# HshMain_v1_2.net
KiCad netlist of a schematic drawn in EAGLE
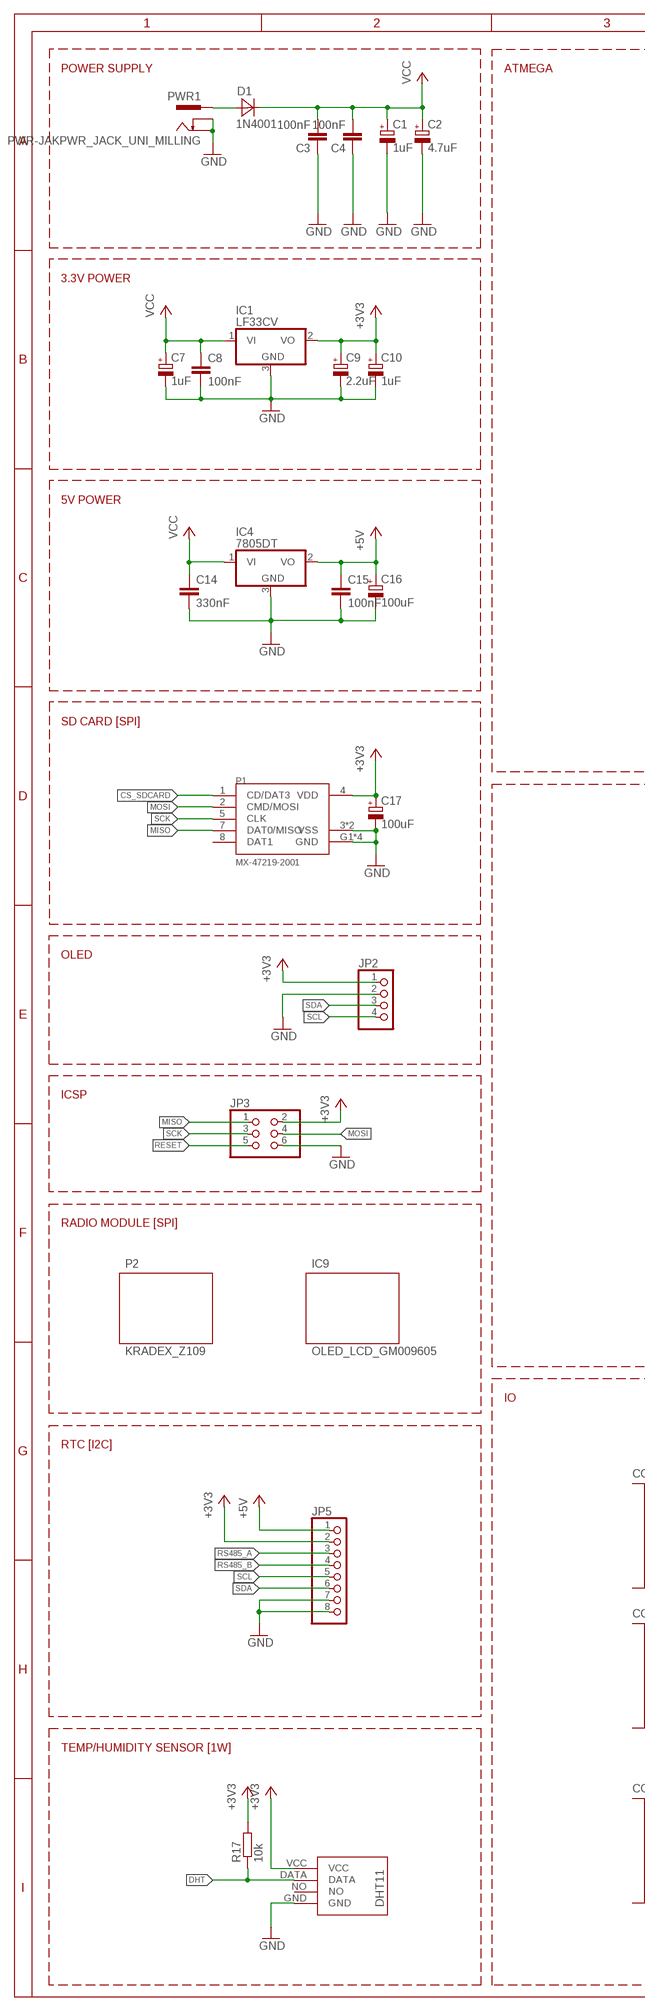
[diagram p0: schematic, sheet 1, part 1 of 2]
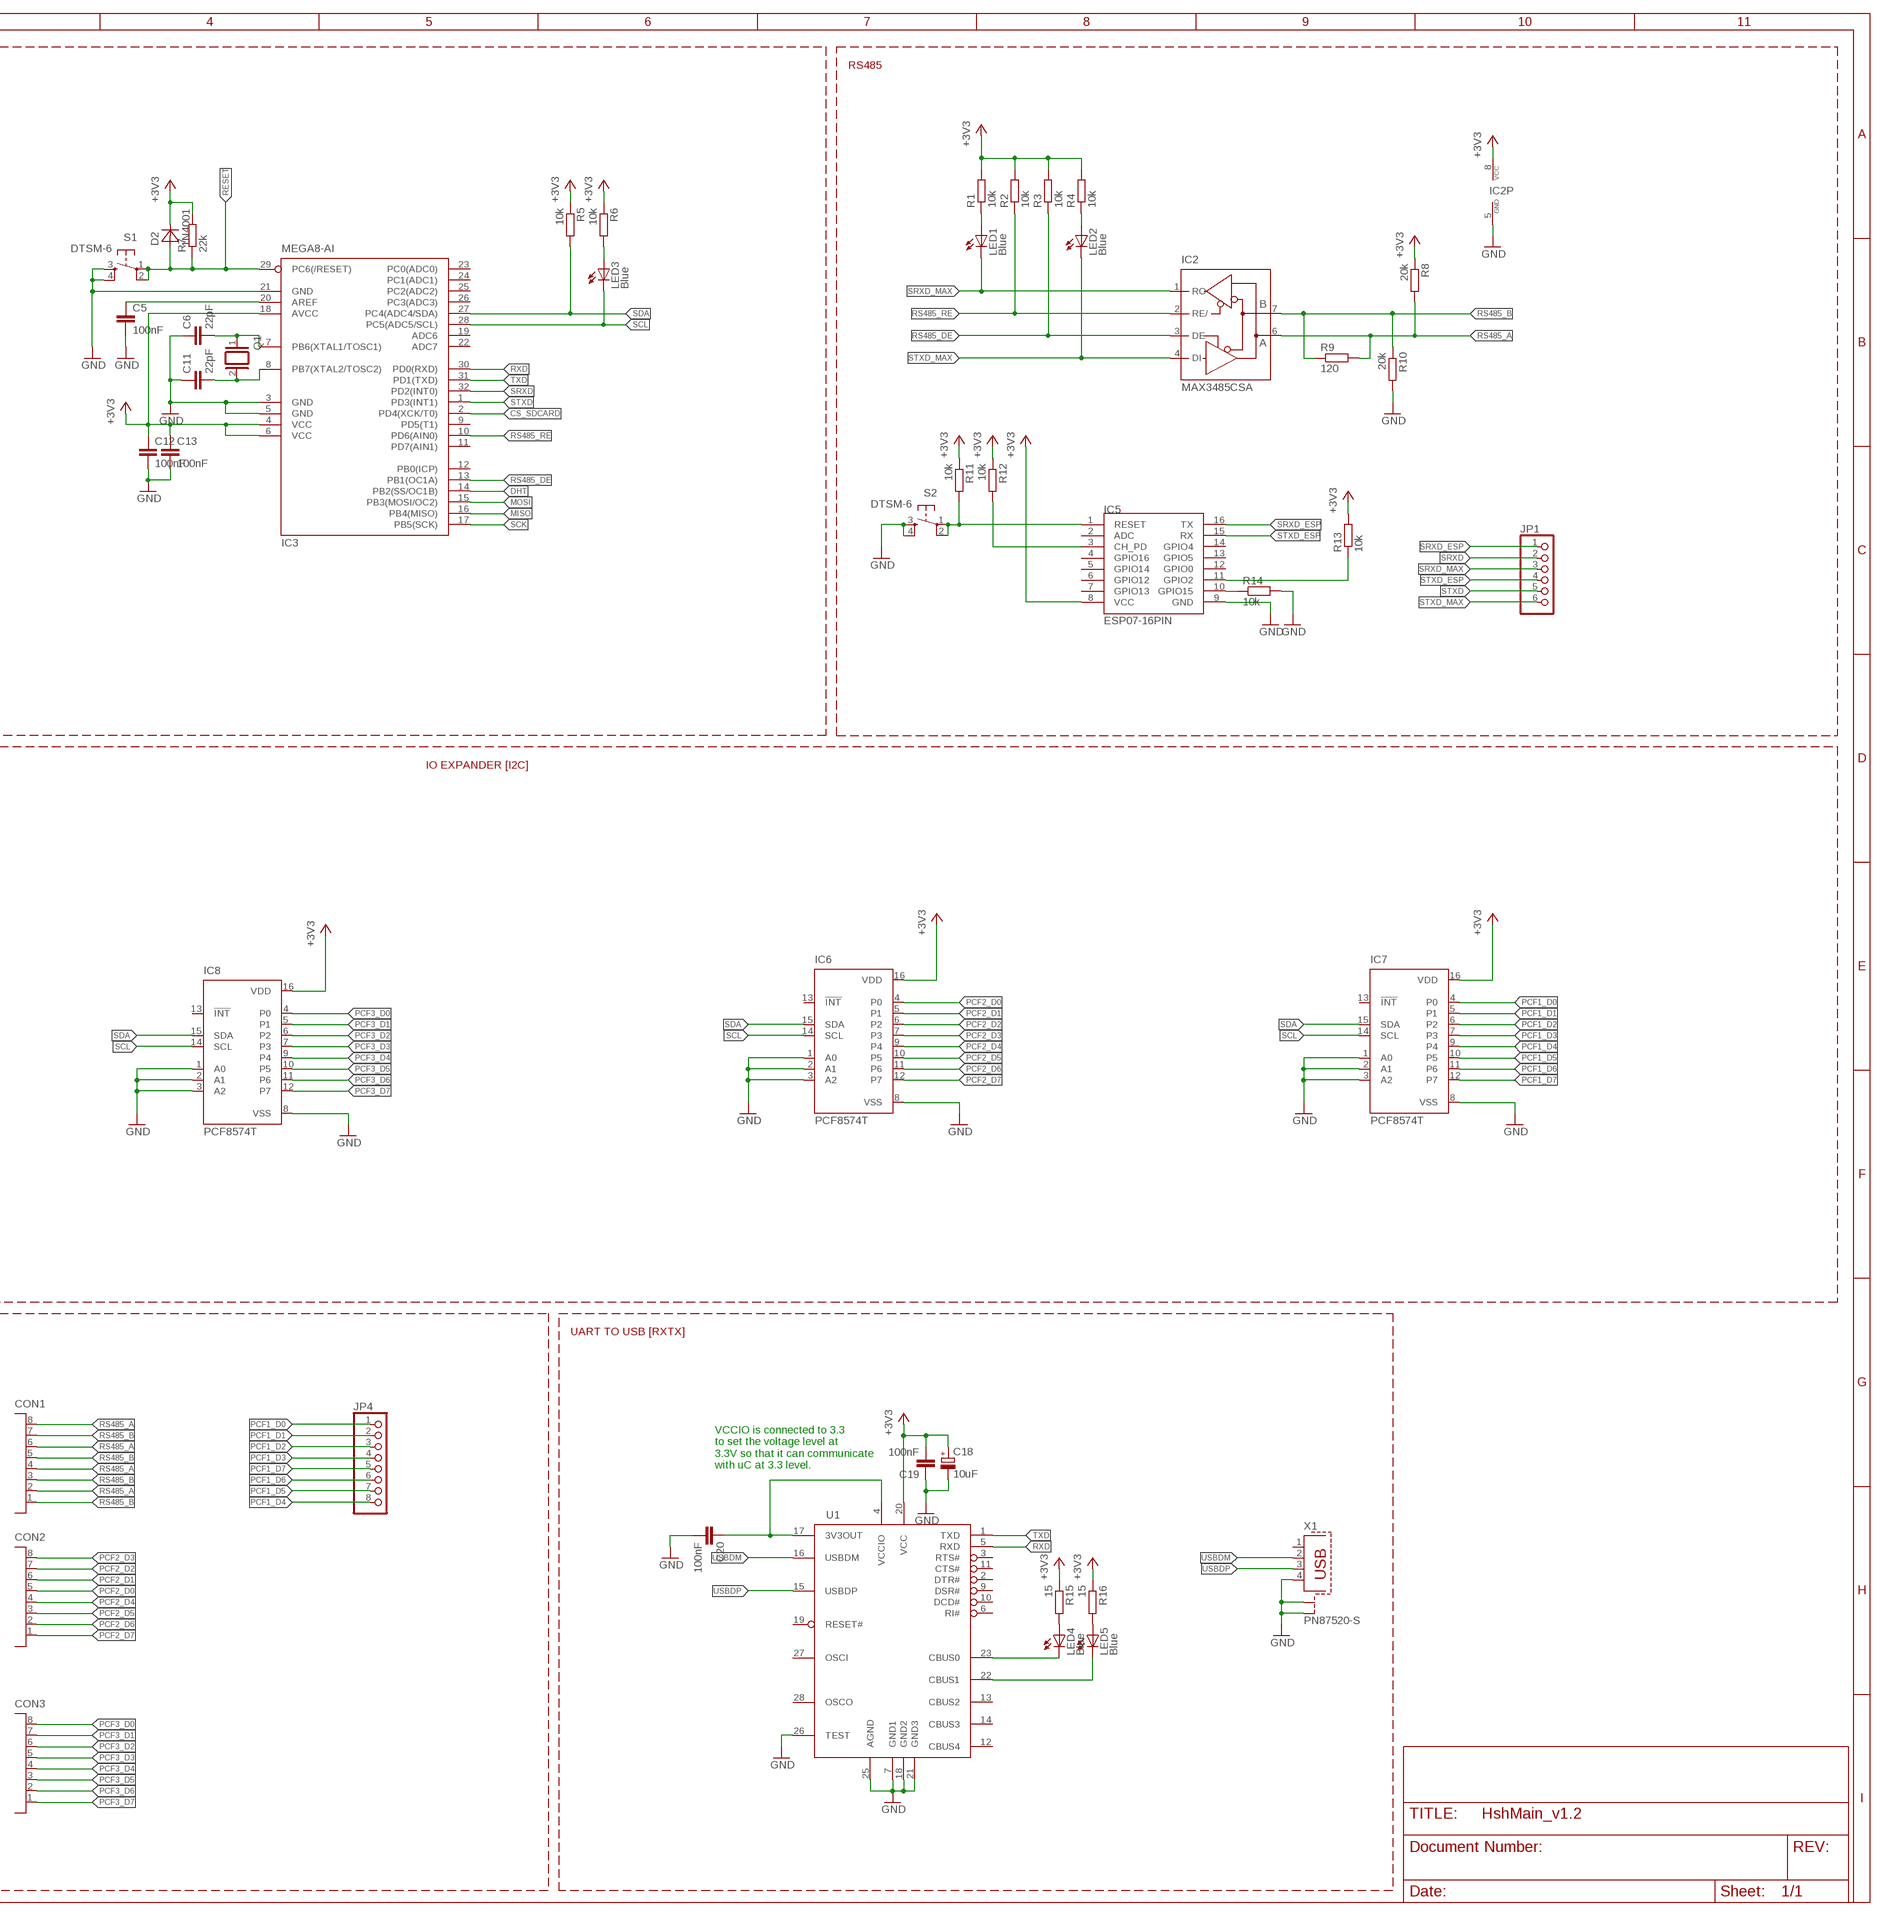
[diagram p1: schematic, sheet 1, part 2 of 2]

(export (version "E")
  (design (tool "Eeschema 10.0.6"))
  (components
    (comp (ref "C1")
      (value "1uF")
      (footprint "eagle-import:PANASONIC_B")
      (libsource (lib "eagle-import") (part "CPOL-EUB"))
    )
    (comp (ref "C2")
      (value "4.7uF")
      (footprint "eagle-import:PANASONIC_B")
      (libsource (lib "eagle-import") (part "CPOL-EUB"))
    )
    (comp (ref "C3")
      (value "100nF")
      (footprint "eagle-import:C0805")
      (libsource (lib "eagle-import") (part "C-EUC0805"))
    )
    (comp (ref "C4")
      (value "100nF")
      (footprint "eagle-import:C0805")
      (libsource (lib "eagle-import") (part "C-EUC0805"))
    )
    (comp (ref "C5")
      (value "100nF")
      (footprint "eagle-import:C0805")
      (libsource (lib "eagle-import") (part "C-EUC0805"))
    )
    (comp (ref "C6")
      (value "22pF")
      (footprint "eagle-import:C0805")
      (libsource (lib "eagle-import") (part "C-EUC0805"))
    )
    (comp (ref "C7")
      (value "1uF")
      (footprint "eagle-import:PANASONIC_B")
      (libsource (lib "eagle-import") (part "CPOL-EUB"))
    )
    (comp (ref "C8")
      (value "100nF")
      (footprint "eagle-import:C0805")
      (libsource (lib "eagle-import") (part "C-EUC0805"))
    )
    (comp (ref "C9")
      (value "2.2uF")
      (footprint "eagle-import:PANASONIC_B")
      (libsource (lib "eagle-import") (part "CPOL-EUB"))
    )
    (comp (ref "C10")
      (value "1uF")
      (footprint "eagle-import:PANASONIC_B")
      (libsource (lib "eagle-import") (part "CPOL-EUB"))
    )
    (comp (ref "C11")
      (value "22pF")
      (footprint "eagle-import:C0805")
      (libsource (lib "eagle-import") (part "C-EUC0805"))
    )
    (comp (ref "C12")
      (value "100nF")
      (footprint "eagle-import:C0805")
      (libsource (lib "eagle-import") (part "C-EUC0805"))
    )
    (comp (ref "C13")
      (value "100nF")
      (footprint "eagle-import:C0805")
      (libsource (lib "eagle-import") (part "C-EUC0805"))
    )
    (comp (ref "C14")
      (value "330nF")
      (footprint "eagle-import:C0805")
      (libsource (lib "eagle-import") (part "C-EUC0805"))
    )
    (comp (ref "C15")
      (value "100nF")
      (footprint "eagle-import:C0805")
      (libsource (lib "eagle-import") (part "C-EUC0805"))
    )
    (comp (ref "C16")
      (value "100uF")
      (footprint "eagle-import:PANASONIC_D")
      (libsource (lib "eagle-import") (part "CPOL-EUD"))
    )
    (comp (ref "C17")
      (value "100uF")
      (footprint "eagle-import:PANASONIC_D")
      (libsource (lib "eagle-import") (part "CPOL-EUD"))
    )
    (comp (ref "C18")
      (value "10uF")
      (footprint "eagle-import:PANASONIC_B")
      (libsource (lib "eagle-import") (part "CPOL-EUB"))
    )
    (comp (ref "C19")
      (value "100nF")
      (footprint "eagle-import:C0805")
      (libsource (lib "eagle-import") (part "C-EUC0805"))
    )
    (comp (ref "C20")
      (value "100nF")
      (footprint "eagle-import:C0805")
      (libsource (lib "eagle-import") (part "C-EUC0805"))
    )
    (comp (ref "CON1")
      (value "15EDGRC-3.81-8P")
      (footprint "eagle-import:15EDGRC-3.81-8P")
      (libsource (lib "eagle-import") (part "15EDGRC-3.81-8P"))
    )
    (comp (ref "CON2")
      (value "15EDGRC-3.81-8P")
      (footprint "eagle-import:15EDGRC-3.81-8P")
      (libsource (lib "eagle-import") (part "15EDGRC-3.81-8P"))
    )
    (comp (ref "CON3")
      (value "15EDGRC-3.81-8P")
      (footprint "eagle-import:15EDGRC-3.81-8P")
      (libsource (lib "eagle-import") (part "15EDGRC-3.81-8P"))
    )
    (comp (ref "D1")
      (value "1N4001")
      (footprint "eagle-import:SMA")
      (libsource (lib "eagle-import") (part "MBRA340T3"))
    )
    (comp (ref "D2")
      (value "1N4001")
      (footprint "eagle-import:SMA")
      (libsource (lib "eagle-import") (part "MBRA340T3"))
    )
    (comp (ref "IC1")
      (value "LF33CV")
      (footprint "eagle-import:TO252")
      (libsource (lib "eagle-import") (part "78DT"))
    )
    (comp (ref "IC2")
      (value "MAX3485CSA")
      (footprint "eagle-import:SO08")
      (fields (field (name "MF") "MAXIM") (field (name "MPN") "MAX481CSA"))
      (libsource (lib "eagle-import") (part "MAX481CSA"))
    )
    (comp (ref "IC3")
      (value "MEGA8-AI")
      (footprint "eagle-import:TQFP32-08")
      (fields (field (name "MPN") "ATMEGA8-16AU"))
      (libsource (lib "eagle-import") (part "MEGA8-AI"))
    )
    (comp (ref "IC4")
      (value "7805DT")
      (footprint "eagle-import:TO252")
      (libsource (lib "eagle-import") (part "linear_78DT05"))
    )
    (comp (ref "IC5")
      (value "ESP07-16PIN")
      (footprint "eagle-import:ESP07-16PIN")
      (libsource (lib "eagle-import") (part "ESP07-16PIN"))
    )
    (comp (ref "IC6")
      (value "PCF8574T")
      (footprint "eagle-import:SO16W")
      (fields (field (name "MPN") "PCF8574T/3,512"))
      (libsource (lib "eagle-import") (part "PCF8574T"))
    )
    (comp (ref "IC7")
      (value "PCF8574T")
      (footprint "eagle-import:SO16W")
      (fields (field (name "MPN") "PCF8574T/3,512"))
      (libsource (lib "eagle-import") (part "PCF8574T"))
    )
    (comp (ref "IC8")
      (value "PCF8574T")
      (footprint "eagle-import:SO16W")
      (fields (field (name "MPN") "PCF8574T/3,512"))
      (libsource (lib "eagle-import") (part "PCF8574T"))
    )
    (comp (ref "IC9")
      (value "OLED_LCD_GM009605")
      (footprint "eagle-import:OLED_LCD_GM009605")
      (libsource (lib "eagle-import") (part "OLED_LCD_GM009605"))
    )
    (comp (ref "IC10")
      (value "DHT11-PION.")
      (footprint "eagle-import:DHT11-PION.")
      (libsource (lib "eagle-import") (part "DHT11-PION."))
    )
    (comp (ref "JP1")
      (value "PINHD-1X6")
      (footprint "eagle-import:1X06")
      (libsource (lib "eagle-import") (part "PINHD-1X6"))
    )
    (comp (ref "JP2")
      (value "PINHD-1X4")
      (footprint "eagle-import:1X04")
      (libsource (lib "eagle-import") (part "PINHD-1X4"))
    )
    (comp (ref "JP3")
      (value "PINHD-2X3")
      (footprint "eagle-import:2X03")
      (libsource (lib "eagle-import") (part "PINHD-2X3"))
    )
    (comp (ref "JP4")
      (value "PINHD-1X8")
      (footprint "eagle-import:1X08")
      (libsource (lib "eagle-import") (part "PINHD-1X8"))
    )
    (comp (ref "JP5")
      (value "PINHD-1X8/90")
      (footprint "eagle-import:1X08_90")
      (libsource (lib "eagle-import") (part "PINHD-1X8/90"))
    )
    (comp (ref "LED1")
      (value "Blue")
      (footprint "eagle-import:SML0805")
      (libsource (lib "eagle-import") (part "LEDSML0805"))
    )
    (comp (ref "LED2")
      (value "Blue")
      (footprint "eagle-import:SML0805")
      (libsource (lib "eagle-import") (part "LEDSML0805"))
    )
    (comp (ref "LED3")
      (value "Blue")
      (footprint "eagle-import:SML0805")
      (libsource (lib "eagle-import") (part "LEDSML0805"))
    )
    (comp (ref "LED4")
      (value "Blue")
      (footprint "eagle-import:SML0805")
      (libsource (lib "eagle-import") (part "LEDSML0805"))
    )
    (comp (ref "LED5")
      (value "Blue")
      (footprint "eagle-import:SML0805")
      (libsource (lib "eagle-import") (part "LEDSML0805"))
    )
    (comp (ref "P1")
      (value "MX-47219-2001")
      (footprint "eagle-import:MX-47219-2001")
      (libsource (lib "eagle-import") (part "MX-47219-2001"))
    )
    (comp (ref "P2")
      (value "KRADEX_Z109")
      (footprint "eagle-import:KRADEX_Z109")
      (libsource (lib "eagle-import") (part "KRADEX_Z109"))
    )
    (comp (ref "PWR1")
      (value "PWR-JAKPWR_JACK_UNI_MILLING")
      (footprint "eagle-import:PWR_JACK_UNI_MILLING")
      (libsource (lib "eagle-import") (part "PWR-JAKPWR_JACK_UNI_MILLING"))
    )
    (comp (ref "Q1")
      (value "XTAL/S")
      (footprint "eagle-import:QS")
      (libsource (lib "eagle-import") (part "XTAL/S"))
    )
    (comp (ref "R1")
      (value "10k")
      (footprint "eagle-import:R0805")
      (libsource (lib "eagle-import") (part "R-EU_R0805"))
    )
    (comp (ref "R2")
      (value "10k")
      (footprint "eagle-import:R0805")
      (libsource (lib "eagle-import") (part "R-EU_R0805"))
    )
    (comp (ref "R3")
      (value "10k")
      (footprint "eagle-import:R0805")
      (libsource (lib "eagle-import") (part "R-EU_R0805"))
    )
    (comp (ref "R4")
      (value "10k")
      (footprint "eagle-import:R0805")
      (libsource (lib "eagle-import") (part "R-EU_R0805"))
    )
    (comp (ref "R5")
      (value "10k")
      (footprint "eagle-import:R0805")
      (libsource (lib "eagle-import") (part "R-EU_R0805"))
    )
    (comp (ref "R6")
      (value "10k")
      (footprint "eagle-import:R0805")
      (libsource (lib "eagle-import") (part "R-EU_R0805"))
    )
    (comp (ref "R7")
      (value "22k")
      (footprint "eagle-import:R0805")
      (libsource (lib "eagle-import") (part "R-EU_R0805"))
    )
    (comp (ref "R8")
      (value "20k")
      (footprint "eagle-import:R0805")
      (libsource (lib "eagle-import") (part "R-EU_R0805"))
    )
    (comp (ref "R9")
      (value "120")
      (footprint "eagle-import:R0805")
      (libsource (lib "eagle-import") (part "R-EU_R0805"))
    )
    (comp (ref "R10")
      (value "20k")
      (footprint "eagle-import:R0805")
      (libsource (lib "eagle-import") (part "R-EU_R0805"))
    )
    (comp (ref "R11")
      (value "10k")
      (footprint "eagle-import:R0805")
      (libsource (lib "eagle-import") (part "R-EU_R0805"))
    )
    (comp (ref "R12")
      (value "10k")
      (footprint "eagle-import:R0805")
      (libsource (lib "eagle-import") (part "R-EU_R0805"))
    )
    (comp (ref "R13")
      (value "10k")
      (footprint "eagle-import:R0805")
      (libsource (lib "eagle-import") (part "R-EU_R0805"))
    )
    (comp (ref "R14")
      (value "10k")
      (footprint "eagle-import:R0805")
      (libsource (lib "eagle-import") (part "R-EU_R0805"))
    )
    (comp (ref "R15")
      (value "15")
      (footprint "eagle-import:R0805")
      (libsource (lib "eagle-import") (part "R-EU_R0805"))
    )
    (comp (ref "R16")
      (value "15")
      (footprint "eagle-import:R0805")
      (libsource (lib "eagle-import") (part "R-EU_R0805"))
    )
    (comp (ref "R17")
      (value "10k")
      (footprint "eagle-import:R0805")
      (libsource (lib "eagle-import") (part "R-EU_R0805"))
    )
    (comp (ref "S1")
      (value "DTSM-6")
      (footprint "eagle-import:DTSM-6")
      (libsource (lib "eagle-import") (part "DTSM-6"))
    )
    (comp (ref "S2")
      (value "DTSM-6")
      (footprint "eagle-import:DTSM-6")
      (libsource (lib "eagle-import") (part "DTSM-6"))
    )
    (comp (ref "U1")
      (value "FT232RL")
      (footprint "eagle-import:SSOP28DB")
      (libsource (lib "eagle-import") (part "FT232RL"))
    )
    (comp (ref "X1")
      (value "PN87520-S")
      (footprint "eagle-import:PN87520-S")
      (libsource (lib "eagle-import") (part "PN87520-S"))
    )
  )
  (nets
    (net (code "1") (name "+3V3") (class "Default")
      (node (ref "C10") (pin "+") (pinfunction "+_+") (pintype "passive"))
      (node (ref "C12") (pin "1") (pinfunction "1_1") (pintype "passive"))
      (node (ref "C13") (pin "1") (pinfunction "1_1") (pintype "passive"))
      (node (ref "C17") (pin "+") (pinfunction "+_+") (pintype "passive"))
      (node (ref "C18") (pin "+") (pinfunction "+_+") (pintype "passive"))
      (node (ref "C19") (pin "2") (pinfunction "2_2") (pintype "passive"))
      (node (ref "C9") (pin "+") (pinfunction "+_+") (pintype "passive"))
      (node (ref "D2") (pin "C") (pinfunction "C_C") (pintype "passive"))
      (node (ref "IC1") (pin "2") (pinfunction "VO_2") (pintype "passive"))
      (node (ref "IC10") (pin "VCC") (pinfunction "VCC_VCC") (pintype "bidirectional"))
      (node (ref "IC2") (pin "8") (pinfunction "VCC_8") (pintype "power_in"))
      (node (ref "IC3") (pin "18") (pinfunction "AVCC_18") (pintype "power_in"))
      (node (ref "IC3") (pin "4") (pinfunction "VCC_4") (pintype "power_in"))
      (node (ref "IC3") (pin "6") (pinfunction "VCC_6") (pintype "power_in"))
      (node (ref "IC5") (pin "8") (pinfunction "VCC_8") (pintype "bidirectional"))
      (node (ref "IC6") (pin "16") (pinfunction "VDD_16") (pintype "power_in"))
      (node (ref "IC7") (pin "16") (pinfunction "VDD_16") (pintype "power_in"))
      (node (ref "IC8") (pin "16") (pinfunction "VDD_16") (pintype "power_in"))
      (node (ref "JP2") (pin "1") (pinfunction "1_1") (pintype "passive"))
      (node (ref "JP3") (pin "2") (pinfunction "2_2") (pintype "passive"))
      (node (ref "JP5") (pin "2") (pinfunction "2_2") (pintype "passive"))
      (node (ref "P1") (pin "4") (pinfunction "VDD_4") (pintype "bidirectional"))
      (node (ref "R1") (pin "2") (pinfunction "2_2") (pintype "passive"))
      (node (ref "R11") (pin "1") (pinfunction "1_1") (pintype "passive"))
      (node (ref "R12") (pin "1") (pinfunction "1_1") (pintype "passive"))
      (node (ref "R13") (pin "2") (pinfunction "2_2") (pintype "passive"))
      (node (ref "R15") (pin "1") (pinfunction "1_1") (pintype "passive"))
      (node (ref "R16") (pin "1") (pinfunction "1_1") (pintype "passive"))
      (node (ref "R17") (pin "2") (pinfunction "2_2") (pintype "passive"))
      (node (ref "R2") (pin "2") (pinfunction "2_2") (pintype "passive"))
      (node (ref "R3") (pin "2") (pinfunction "2_2") (pintype "passive"))
      (node (ref "R4") (pin "2") (pinfunction "2_2") (pintype "passive"))
      (node (ref "R5") (pin "1") (pinfunction "1_1") (pintype "passive"))
      (node (ref "R6") (pin "1") (pinfunction "1_1") (pintype "passive"))
      (node (ref "R7") (pin "2") (pinfunction "2_2") (pintype "passive"))
      (node (ref "R8") (pin "1") (pinfunction "1_1") (pintype "passive"))
      (node (ref "U1") (pin "20") (pinfunction "VCC_20") (pintype "power_in"))
    )
    (net (code "2") (name "+5V") (class "Default")
      (node (ref "C15") (pin "1") (pinfunction "1_1") (pintype "passive"))
      (node (ref "C16") (pin "+") (pinfunction "+_+") (pintype "passive"))
      (node (ref "IC4") (pin "2") (pinfunction "VO_2") (pintype "passive"))
      (node (ref "JP5") (pin "1") (pinfunction "1_1") (pintype "passive"))
    )
    (net (code "3") (name "CS_SDCARD") (class "Default")
      (node (ref "IC3") (pin "2") (pinfunction "PD4(XCK/T0)_2") (pintype "bidirectional"))
      (node (ref "P1") (pin "1") (pinfunction "CD/DAT3_1") (pintype "bidirectional"))
    )
    (net (code "4") (name "DHT") (class "Default")
      (node (ref "IC10") (pin "DATA") (pinfunction "DATA_DATA") (pintype "bidirectional"))
      (node (ref "IC3") (pin "14") (pinfunction "PB2(SS/OC1B)_14") (pintype "bidirectional"))
      (node (ref "R17") (pin "1") (pinfunction "1_1") (pintype "passive"))
    )
    (net (code "5") (name "GND") (class "Default")
      (node (ref "C1") (pin "-") (pinfunction "-_-") (pintype "passive"))
      (node (ref "C10") (pin "-") (pinfunction "-_-") (pintype "passive"))
      (node (ref "C11") (pin "1") (pinfunction "1_1") (pintype "passive"))
      (node (ref "C12") (pin "2") (pinfunction "2_2") (pintype "passive"))
      (node (ref "C13") (pin "2") (pinfunction "2_2") (pintype "passive"))
      (node (ref "C14") (pin "2") (pinfunction "2_2") (pintype "passive"))
      (node (ref "C15") (pin "2") (pinfunction "2_2") (pintype "passive"))
      (node (ref "C16") (pin "-") (pinfunction "-_-") (pintype "passive"))
      (node (ref "C17") (pin "-") (pinfunction "-_-") (pintype "passive"))
      (node (ref "C18") (pin "-") (pinfunction "-_-") (pintype "passive"))
      (node (ref "C19") (pin "1") (pinfunction "1_1") (pintype "passive"))
      (node (ref "C2") (pin "-") (pinfunction "-_-") (pintype "passive"))
      (node (ref "C20") (pin "2") (pinfunction "2_2") (pintype "passive"))
      (node (ref "C3") (pin "1") (pinfunction "1_1") (pintype "passive"))
      (node (ref "C4") (pin "1") (pinfunction "1_1") (pintype "passive"))
      (node (ref "C5") (pin "2") (pinfunction "2_2") (pintype "passive"))
      (node (ref "C6") (pin "1") (pinfunction "1_1") (pintype "passive"))
      (node (ref "C7") (pin "-") (pinfunction "-_-") (pintype "passive"))
      (node (ref "C8") (pin "2") (pinfunction "2_2") (pintype "passive"))
      (node (ref "C9") (pin "-") (pinfunction "-_-") (pintype "passive"))
      (node (ref "IC1") (pin "3") (pinfunction "GND_3") (pintype "passive"))
      (node (ref "IC10") (pin "GND") (pinfunction "GND_GND") (pintype "bidirectional"))
      (node (ref "IC2") (pin "5") (pinfunction "GND_5") (pintype "power_in"))
      (node (ref "IC3") (pin "21") (pinfunction "GND_21") (pintype "power_in"))
      (node (ref "IC3") (pin "3") (pinfunction "GND_3") (pintype "power_in"))
      (node (ref "IC3") (pin "5") (pinfunction "GND_5") (pintype "power_in"))
      (node (ref "IC4") (pin "3") (pinfunction "GND_3") (pintype "passive"))
      (node (ref "IC5") (pin "9") (pinfunction "GND_9") (pintype "bidirectional"))
      (node (ref "IC6") (pin "1") (pinfunction "A0_1") (pintype "input"))
      (node (ref "IC6") (pin "2") (pinfunction "A1_2") (pintype "input"))
      (node (ref "IC6") (pin "3") (pinfunction "A2_3") (pintype "input"))
      (node (ref "IC6") (pin "8") (pinfunction "VSS_8") (pintype "power_in"))
      (node (ref "IC7") (pin "1") (pinfunction "A0_1") (pintype "input"))
      (node (ref "IC7") (pin "2") (pinfunction "A1_2") (pintype "input"))
      (node (ref "IC7") (pin "3") (pinfunction "A2_3") (pintype "input"))
      (node (ref "IC7") (pin "8") (pinfunction "VSS_8") (pintype "power_in"))
      (node (ref "IC8") (pin "1") (pinfunction "A0_1") (pintype "input"))
      (node (ref "IC8") (pin "2") (pinfunction "A1_2") (pintype "input"))
      (node (ref "IC8") (pin "3") (pinfunction "A2_3") (pintype "input"))
      (node (ref "IC8") (pin "8") (pinfunction "VSS_8") (pintype "power_in"))
      (node (ref "JP2") (pin "2") (pinfunction "2_2") (pintype "passive"))
      (node (ref "JP3") (pin "6") (pinfunction "6_6") (pintype "passive"))
      (node (ref "JP5") (pin "7") (pinfunction "7_7") (pintype "passive"))
      (node (ref "JP5") (pin "8") (pinfunction "8_8") (pintype "passive"))
      (node (ref "P1") (pin "3") (pinfunction "VSS_3") (pintype "bidirectional"))
      (node (ref "P1") (pin "6") (pinfunction "VSS_6") (pintype "bidirectional"))
      (node (ref "P1") (pin "G1") (pinfunction "GND_G1") (pintype "bidirectional"))
      (node (ref "P1") (pin "G2") (pinfunction "GND_G2") (pintype "bidirectional"))
      (node (ref "P1") (pin "G3") (pinfunction "GND_G3") (pintype "bidirectional"))
      (node (ref "P1") (pin "G4") (pinfunction "GND_G4") (pintype "bidirectional"))
      (node (ref "PWR1") (pin "-") (pinfunction "-_-") (pintype "passive"))
      (node (ref "PWR1") (pin "--") (pinfunction "--_--") (pintype "passive"))
      (node (ref "PWR1") (pin "--1") (pinfunction "--_--1") (pintype "passive"))
      (node (ref "PWR1") (pin "--2") (pinfunction "--_--2") (pintype "passive"))
      (node (ref "PWR1") (pin "--3") (pinfunction "--_--3") (pintype "passive"))
      (node (ref "PWR1") (pin "--4") (pinfunction "--_--4") (pintype "passive"))
      (node (ref "PWR1") (pin "--5") (pinfunction "--_--5") (pintype "passive"))
      (node (ref "PWR1") (pin "--6") (pinfunction "--_--6") (pintype "passive"))
      (node (ref "PWR1") (pin "--7") (pinfunction "--_--7") (pintype "passive"))
      (node (ref "PWR1") (pin "--8") (pinfunction "--_--8") (pintype "passive"))
      (node (ref "PWR1") (pin "-1") (pinfunction "-_-1") (pintype "passive"))
      (node (ref "PWR1") (pin "-2") (pinfunction "-_-2") (pintype "passive"))
      (node (ref "PWR1") (pin "-3") (pinfunction "-_-3") (pintype "passive"))
      (node (ref "PWR1") (pin "-4") (pinfunction "-_-4") (pintype "passive"))
      (node (ref "PWR1") (pin "-5") (pinfunction "-_-5") (pintype "passive"))
      (node (ref "PWR1") (pin "-6") (pinfunction "-_-6") (pintype "passive"))
      (node (ref "PWR1") (pin "-7") (pinfunction "-_-7") (pintype "passive"))
      (node (ref "PWR1") (pin "-8") (pinfunction "-_-8") (pintype "passive"))
      (node (ref "R10") (pin "2") (pinfunction "2_2") (pintype "passive"))
      (node (ref "R14") (pin "2") (pinfunction "2_2") (pintype "passive"))
      (node (ref "S1") (pin "3") (pinfunction "3_3") (pintype "passive"))
      (node (ref "S1") (pin "4") (pinfunction "4_4") (pintype "passive"))
      (node (ref "S2") (pin "3") (pinfunction "3_3") (pintype "passive"))
      (node (ref "S2") (pin "4") (pinfunction "4_4") (pintype "passive"))
      (node (ref "U1") (pin "18") (pinfunction "GND2_18") (pintype "power_in"))
      (node (ref "U1") (pin "21") (pinfunction "GND3_21") (pintype "power_in"))
      (node (ref "U1") (pin "25") (pinfunction "AGND_25") (pintype "power_in"))
      (node (ref "U1") (pin "26") (pinfunction "TEST_26") (pintype "input"))
      (node (ref "U1") (pin "7") (pinfunction "GND1_7") (pintype "power_in"))
      (node (ref "X1") (pin "4") (pinfunction "4_4") (pintype "passive"))
      (node (ref "X1") (pin "S1") (pinfunction "S1_S1") (pintype "passive"))
      (node (ref "X1") (pin "S2") (pinfunction "S2_S2") (pintype "passive"))
    )
    (net (code "6") (name "MISO") (class "Default")
      (node (ref "IC3") (pin "16") (pinfunction "PB4(MISO)_16") (pintype "bidirectional"))
      (node (ref "JP3") (pin "1") (pinfunction "1_1") (pintype "passive"))
      (node (ref "P1") (pin "7") (pinfunction "DAT0/MISO_7") (pintype "bidirectional"))
    )
    (net (code "7") (name "MOSI") (class "Default")
      (node (ref "IC3") (pin "15") (pinfunction "PB3(MOSI/OC2)_15") (pintype "bidirectional"))
      (node (ref "JP3") (pin "4") (pinfunction "4_4") (pintype "passive"))
      (node (ref "P1") (pin "2") (pinfunction "CMD/MOSI_2") (pintype "bidirectional"))
    )
    (net (code "8") (name "Net-(D1-PadA)") (class "Default")
      (node (ref "D1") (pin "A") (pinfunction "A_A") (pintype "passive"))
      (node (ref "PWR1") (pin "+") (pinfunction "+_+") (pintype "passive"))
      (node (ref "PWR1") (pin "+1") (pinfunction "+_+1") (pintype "passive"))
      (node (ref "PWR1") (pin "+2") (pinfunction "+_+2") (pintype "passive"))
      (node (ref "PWR1") (pin "+3") (pinfunction "+_+3") (pintype "passive"))
      (node (ref "PWR1") (pin "+4") (pinfunction "+_+4") (pintype "passive"))
      (node (ref "PWR1") (pin "+5") (pinfunction "+_+5") (pintype "passive"))
      (node (ref "PWR1") (pin "+6") (pinfunction "+_+6") (pintype "passive"))
      (node (ref "PWR1") (pin "+7") (pinfunction "+_+7") (pintype "passive"))
      (node (ref "PWR1") (pin "+8") (pinfunction "+_+8") (pintype "passive"))
    )
    (net (code "9") (name "Net-(IC3-AREF)") (class "Default")
      (node (ref "C5") (pin "1") (pinfunction "1_1") (pintype "passive"))
      (node (ref "IC3") (pin "20") (pinfunction "AREF_20") (pintype "passive"))
    )
    (net (code "10") (name "Net-(IC3-PB6(XTAL1{slash}TOSC1))") (class "Default")
      (node (ref "C6") (pin "2") (pinfunction "2_2") (pintype "passive"))
      (node (ref "IC3") (pin "7") (pinfunction "PB6(XTAL1/TOSC1)_7") (pintype "bidirectional"))
      (node (ref "Q1") (pin "1") (pinfunction "1_1") (pintype "passive"))
    )
    (net (code "11") (name "Net-(IC3-PB7(XTAL2{slash}TOSC2))") (class "Default")
      (node (ref "C11") (pin "2") (pinfunction "2_2") (pintype "passive"))
      (node (ref "IC3") (pin "8") (pinfunction "PB7(XTAL2/TOSC2)_8") (pintype "bidirectional"))
      (node (ref "Q1") (pin "2") (pinfunction "2_2") (pintype "passive"))
    )
    (net (code "12") (name "Net-(IC5-CH_PD)") (class "Default")
      (node (ref "IC5") (pin "3") (pinfunction "CH_PD_3") (pintype "bidirectional"))
      (node (ref "R12") (pin "2") (pinfunction "2_2") (pintype "passive"))
    )
    (net (code "13") (name "Net-(IC5-GPIO2)") (class "Default")
      (node (ref "IC5") (pin "11") (pinfunction "GPIO2_11") (pintype "bidirectional"))
      (node (ref "R13") (pin "1") (pinfunction "1_1") (pintype "passive"))
    )
    (net (code "14") (name "Net-(IC5-GPIO15)") (class "Default")
      (node (ref "IC5") (pin "10") (pinfunction "GPIO15_10") (pintype "bidirectional"))
      (node (ref "R14") (pin "1") (pinfunction "1_1") (pintype "passive"))
    )
    (net (code "15") (name "Net-(IC5-RESET)") (class "Default")
      (node (ref "IC5") (pin "1") (pinfunction "RESET_1") (pintype "bidirectional"))
      (node (ref "R11") (pin "2") (pinfunction "2_2") (pintype "passive"))
      (node (ref "S2") (pin "1") (pinfunction "1_1") (pintype "passive"))
      (node (ref "S2") (pin "2") (pinfunction "2_2") (pintype "passive"))
    )
    (net (code "16") (name "Net-(LED1-PadA)") (class "Default")
      (node (ref "LED1") (pin "A") (pinfunction "A_A") (pintype "passive"))
      (node (ref "R1") (pin "1") (pinfunction "1_1") (pintype "passive"))
    )
    (net (code "17") (name "Net-(LED2-PadA)") (class "Default")
      (node (ref "LED2") (pin "A") (pinfunction "A_A") (pintype "passive"))
      (node (ref "R4") (pin "1") (pinfunction "1_1") (pintype "passive"))
    )
    (net (code "18") (name "Net-(LED3-PadA)") (class "Default")
      (node (ref "LED3") (pin "A") (pinfunction "A_A") (pintype "passive"))
      (node (ref "R6") (pin "2") (pinfunction "2_2") (pintype "passive"))
    )
    (net (code "19") (name "Net-(LED4-PadA)") (class "Default")
      (node (ref "LED4") (pin "A") (pinfunction "A_A") (pintype "passive"))
      (node (ref "R15") (pin "2") (pinfunction "2_2") (pintype "passive"))
    )
    (net (code "20") (name "Net-(LED5-PadA)") (class "Default")
      (node (ref "LED5") (pin "A") (pinfunction "A_A") (pintype "passive"))
      (node (ref "R16") (pin "2") (pinfunction "2_2") (pintype "passive"))
    )
    (net (code "21") (name "Net-(U1-3V3OUT)") (class "Default")
      (node (ref "C20") (pin "1") (pinfunction "1_1") (pintype "passive"))
      (node (ref "U1") (pin "17") (pinfunction "3V3OUT_17") (pintype "output"))
      (node (ref "U1") (pin "4") (pinfunction "VCCIO_4") (pintype "power_in"))
    )
    (net (code "22") (name "Net-(U1-CBUS0)") (class "Default")
      (node (ref "LED4") (pin "C") (pinfunction "C_C") (pintype "passive"))
      (node (ref "U1") (pin "23") (pinfunction "CBUS0_23") (pintype "bidirectional"))
    )
    (net (code "23") (name "Net-(U1-CBUS1)") (class "Default")
      (node (ref "LED5") (pin "C") (pinfunction "C_C") (pintype "passive"))
      (node (ref "U1") (pin "22") (pinfunction "CBUS1_22") (pintype "bidirectional"))
    )
    (net (code "24") (name "PCF1_D0") (class "Default")
      (node (ref "IC7") (pin "4") (pinfunction "P0_4") (pintype "bidirectional"))
      (node (ref "JP4") (pin "1") (pinfunction "1_1") (pintype "passive"))
    )
    (net (code "25") (name "PCF1_D1") (class "Default")
      (node (ref "IC7") (pin "5") (pinfunction "P1_5") (pintype "bidirectional"))
      (node (ref "JP4") (pin "2") (pinfunction "2_2") (pintype "passive"))
    )
    (net (code "26") (name "PCF1_D2") (class "Default")
      (node (ref "IC7") (pin "6") (pinfunction "P2_6") (pintype "bidirectional"))
      (node (ref "JP4") (pin "3") (pinfunction "3_3") (pintype "passive"))
    )
    (net (code "27") (name "PCF1_D3") (class "Default")
      (node (ref "IC7") (pin "7") (pinfunction "P3_7") (pintype "bidirectional"))
      (node (ref "JP4") (pin "4") (pinfunction "4_4") (pintype "passive"))
    )
    (net (code "28") (name "PCF1_D4") (class "Default")
      (node (ref "IC7") (pin "9") (pinfunction "P4_9") (pintype "bidirectional"))
      (node (ref "JP4") (pin "8") (pinfunction "8_8") (pintype "passive"))
    )
    (net (code "29") (name "PCF1_D5") (class "Default")
      (node (ref "IC7") (pin "10") (pinfunction "P5_10") (pintype "bidirectional"))
      (node (ref "JP4") (pin "7") (pinfunction "7_7") (pintype "passive"))
    )
    (net (code "30") (name "PCF1_D6") (class "Default")
      (node (ref "IC7") (pin "11") (pinfunction "P6_11") (pintype "bidirectional"))
      (node (ref "JP4") (pin "6") (pinfunction "6_6") (pintype "passive"))
    )
    (net (code "31") (name "PCF1_D7") (class "Default")
      (node (ref "IC7") (pin "12") (pinfunction "P7_12") (pintype "bidirectional"))
      (node (ref "JP4") (pin "5") (pinfunction "5_5") (pintype "passive"))
    )
    (net (code "32") (name "PCF2_D0") (class "Default")
      (node (ref "CON2") (pin "5") (pinfunction "P$5_5") (pintype "bidirectional"))
      (node (ref "IC6") (pin "4") (pinfunction "P0_4") (pintype "bidirectional"))
    )
    (net (code "33") (name "PCF2_D1") (class "Default")
      (node (ref "CON2") (pin "6") (pinfunction "P$6_6") (pintype "bidirectional"))
      (node (ref "IC6") (pin "5") (pinfunction "P1_5") (pintype "bidirectional"))
    )
    (net (code "34") (name "PCF2_D2") (class "Default")
      (node (ref "CON2") (pin "7") (pinfunction "P$7_7") (pintype "bidirectional"))
      (node (ref "IC6") (pin "6") (pinfunction "P2_6") (pintype "bidirectional"))
    )
    (net (code "35") (name "PCF2_D3") (class "Default")
      (node (ref "CON2") (pin "8") (pinfunction "P$8_8") (pintype "bidirectional"))
      (node (ref "IC6") (pin "7") (pinfunction "P3_7") (pintype "bidirectional"))
    )
    (net (code "36") (name "PCF2_D4") (class "Default")
      (node (ref "CON2") (pin "4") (pinfunction "P$4_4") (pintype "bidirectional"))
      (node (ref "IC6") (pin "9") (pinfunction "P4_9") (pintype "bidirectional"))
    )
    (net (code "37") (name "PCF2_D5") (class "Default")
      (node (ref "CON2") (pin "3") (pinfunction "P$3_3") (pintype "bidirectional"))
      (node (ref "IC6") (pin "10") (pinfunction "P5_10") (pintype "bidirectional"))
    )
    (net (code "38") (name "PCF2_D6") (class "Default")
      (node (ref "CON2") (pin "2") (pinfunction "P$2_2") (pintype "bidirectional"))
      (node (ref "IC6") (pin "11") (pinfunction "P6_11") (pintype "bidirectional"))
    )
    (net (code "39") (name "PCF2_D7") (class "Default")
      (node (ref "CON2") (pin "1") (pinfunction "P$1_1") (pintype "bidirectional"))
      (node (ref "IC6") (pin "12") (pinfunction "P7_12") (pintype "bidirectional"))
    )
    (net (code "40") (name "PCF3_D0") (class "Default")
      (node (ref "CON3") (pin "8") (pinfunction "P$8_8") (pintype "bidirectional"))
      (node (ref "IC8") (pin "4") (pinfunction "P0_4") (pintype "bidirectional"))
    )
    (net (code "41") (name "PCF3_D1") (class "Default")
      (node (ref "CON3") (pin "7") (pinfunction "P$7_7") (pintype "bidirectional"))
      (node (ref "IC8") (pin "5") (pinfunction "P1_5") (pintype "bidirectional"))
    )
    (net (code "42") (name "PCF3_D2") (class "Default")
      (node (ref "CON3") (pin "6") (pinfunction "P$6_6") (pintype "bidirectional"))
      (node (ref "IC8") (pin "6") (pinfunction "P2_6") (pintype "bidirectional"))
    )
    (net (code "43") (name "PCF3_D3") (class "Default")
      (node (ref "CON3") (pin "5") (pinfunction "P$5_5") (pintype "bidirectional"))
      (node (ref "IC8") (pin "7") (pinfunction "P3_7") (pintype "bidirectional"))
    )
    (net (code "44") (name "PCF3_D4") (class "Default")
      (node (ref "CON3") (pin "4") (pinfunction "P$4_4") (pintype "bidirectional"))
      (node (ref "IC8") (pin "9") (pinfunction "P4_9") (pintype "bidirectional"))
    )
    (net (code "45") (name "PCF3_D5") (class "Default")
      (node (ref "CON3") (pin "3") (pinfunction "P$3_3") (pintype "bidirectional"))
      (node (ref "IC8") (pin "10") (pinfunction "P5_10") (pintype "bidirectional"))
    )
    (net (code "46") (name "PCF3_D6") (class "Default")
      (node (ref "CON3") (pin "2") (pinfunction "P$2_2") (pintype "bidirectional"))
      (node (ref "IC8") (pin "11") (pinfunction "P6_11") (pintype "bidirectional"))
    )
    (net (code "47") (name "PCF3_D7") (class "Default")
      (node (ref "CON3") (pin "1") (pinfunction "P$1_1") (pintype "bidirectional"))
      (node (ref "IC8") (pin "12") (pinfunction "P7_12") (pintype "bidirectional"))
    )
    (net (code "48") (name "RESET") (class "Default")
      (node (ref "D2") (pin "A") (pinfunction "A_A") (pintype "passive"))
      (node (ref "IC3") (pin "29") (pinfunction "PC6(/RESET)_29") (pintype "bidirectional"))
      (node (ref "JP3") (pin "5") (pinfunction "5_5") (pintype "passive"))
      (node (ref "R7") (pin "1") (pinfunction "1_1") (pintype "passive"))
      (node (ref "S1") (pin "1") (pinfunction "1_1") (pintype "passive"))
      (node (ref "S1") (pin "2") (pinfunction "2_2") (pintype "passive"))
    )
    (net (code "49") (name "RS485_A") (class "Default")
      (node (ref "CON1") (pin "2") (pinfunction "P$2_2") (pintype "bidirectional"))
      (node (ref "CON1") (pin "4") (pinfunction "P$4_4") (pintype "bidirectional"))
      (node (ref "CON1") (pin "6") (pinfunction "P$6_6") (pintype "bidirectional"))
      (node (ref "CON1") (pin "8") (pinfunction "P$8_8") (pintype "bidirectional"))
      (node (ref "IC2") (pin "6") (pinfunction "A_6") (pintype "passive"))
      (node (ref "JP5") (pin "3") (pinfunction "3_3") (pintype "passive"))
      (node (ref "R8") (pin "2") (pinfunction "2_2") (pintype "passive"))
      (node (ref "R9") (pin "2") (pinfunction "2_2") (pintype "passive"))
    )
    (net (code "50") (name "RS485_B") (class "Default")
      (node (ref "CON1") (pin "1") (pinfunction "P$1_1") (pintype "bidirectional"))
      (node (ref "CON1") (pin "3") (pinfunction "P$3_3") (pintype "bidirectional"))
      (node (ref "CON1") (pin "5") (pinfunction "P$5_5") (pintype "bidirectional"))
      (node (ref "CON1") (pin "7") (pinfunction "P$7_7") (pintype "bidirectional"))
      (node (ref "IC2") (pin "7") (pinfunction "B_7") (pintype "passive"))
      (node (ref "JP5") (pin "4") (pinfunction "4_4") (pintype "passive"))
      (node (ref "R10") (pin "1") (pinfunction "1_1") (pintype "passive"))
      (node (ref "R9") (pin "1") (pinfunction "1_1") (pintype "passive"))
    )
    (net (code "51") (name "RS485_DE") (class "Default")
      (node (ref "IC2") (pin "3") (pinfunction "DE_3") (pintype "input"))
      (node (ref "IC3") (pin "13") (pinfunction "PB1(OC1A)_13") (pintype "bidirectional"))
      (node (ref "R3") (pin "1") (pinfunction "1_1") (pintype "passive"))
    )
    (net (code "52") (name "RS485_RE") (class "Default")
      (node (ref "IC2") (pin "2") (pinfunction "RE/_2") (pintype "input"))
      (node (ref "IC3") (pin "10") (pinfunction "PD6(AIN0)_10") (pintype "bidirectional"))
      (node (ref "R2") (pin "1") (pinfunction "1_1") (pintype "passive"))
    )
    (net (code "53") (name "RXD") (class "Default")
      (node (ref "IC3") (pin "30") (pinfunction "PD0(RXD)_30") (pintype "bidirectional"))
      (node (ref "U1") (pin "5") (pinfunction "RXD_5") (pintype "input"))
    )
    (net (code "54") (name "SCK") (class "Default")
      (node (ref "IC3") (pin "17") (pinfunction "PB5(SCK)_17") (pintype "bidirectional"))
      (node (ref "JP3") (pin "3") (pinfunction "3_3") (pintype "passive"))
      (node (ref "P1") (pin "5") (pinfunction "CLK_5") (pintype "bidirectional"))
    )
    (net (code "55") (name "SCL") (class "Default")
      (node (ref "IC3") (pin "28") (pinfunction "PC5(ADC5/SCL)_28") (pintype "bidirectional"))
      (node (ref "IC6") (pin "14") (pinfunction "SCL_14") (pintype "input"))
      (node (ref "IC7") (pin "14") (pinfunction "SCL_14") (pintype "input"))
      (node (ref "IC8") (pin "14") (pinfunction "SCL_14") (pintype "input"))
      (node (ref "JP2") (pin "4") (pinfunction "4_4") (pintype "passive"))
      (node (ref "JP5") (pin "5") (pinfunction "5_5") (pintype "passive"))
      (node (ref "LED3") (pin "C") (pinfunction "C_C") (pintype "passive"))
    )
    (net (code "56") (name "SDA") (class "Default")
      (node (ref "IC3") (pin "27") (pinfunction "PC4(ADC4/SDA)_27") (pintype "bidirectional"))
      (node (ref "IC6") (pin "15") (pinfunction "SDA_15") (pintype "bidirectional"))
      (node (ref "IC7") (pin "15") (pinfunction "SDA_15") (pintype "bidirectional"))
      (node (ref "IC8") (pin "15") (pinfunction "SDA_15") (pintype "bidirectional"))
      (node (ref "JP2") (pin "3") (pinfunction "3_3") (pintype "passive"))
      (node (ref "JP5") (pin "6") (pinfunction "6_6") (pintype "passive"))
      (node (ref "R5") (pin "2") (pinfunction "2_2") (pintype "passive"))
    )
    (net (code "57") (name "SRXD") (class "Default")
      (node (ref "IC3") (pin "32") (pinfunction "PD2(INT0)_32") (pintype "bidirectional"))
      (node (ref "JP1") (pin "2") (pinfunction "2_2") (pintype "passive"))
    )
    (net (code "58") (name "SRXD_ESP") (class "Default")
      (node (ref "IC5") (pin "16") (pinfunction "TX_16") (pintype "bidirectional"))
      (node (ref "JP1") (pin "1") (pinfunction "1_1") (pintype "passive"))
    )
    (net (code "59") (name "SRXD_MAX") (class "Default")
      (node (ref "IC2") (pin "1") (pinfunction "RO_1") (pintype "output"))
      (node (ref "JP1") (pin "3") (pinfunction "3_3") (pintype "passive"))
      (node (ref "LED1") (pin "C") (pinfunction "C_C") (pintype "passive"))
    )
    (net (code "60") (name "STXD") (class "Default")
      (node (ref "IC3") (pin "1") (pinfunction "PD3(INT1)_1") (pintype "bidirectional"))
      (node (ref "JP1") (pin "5") (pinfunction "5_5") (pintype "passive"))
    )
    (net (code "61") (name "STXD_ESP") (class "Default")
      (node (ref "IC5") (pin "15") (pinfunction "RX_15") (pintype "bidirectional"))
      (node (ref "JP1") (pin "4") (pinfunction "4_4") (pintype "passive"))
    )
    (net (code "62") (name "STXD_MAX") (class "Default")
      (node (ref "IC2") (pin "4") (pinfunction "DI_4") (pintype "input"))
      (node (ref "JP1") (pin "6") (pinfunction "6_6") (pintype "passive"))
      (node (ref "LED2") (pin "C") (pinfunction "C_C") (pintype "passive"))
    )
    (net (code "63") (name "TXD") (class "Default")
      (node (ref "IC3") (pin "31") (pinfunction "PD1(TXD)_31") (pintype "bidirectional"))
      (node (ref "U1") (pin "1") (pinfunction "TXD_1") (pintype "output"))
    )
    (net (code "64") (name "USBDM") (class "Default")
      (node (ref "U1") (pin "16") (pinfunction "USBDM_16") (pintype "bidirectional"))
      (node (ref "X1") (pin "2") (pinfunction "2_2") (pintype "passive"))
    )
    (net (code "65") (name "USBDP") (class "Default")
      (node (ref "U1") (pin "15") (pinfunction "USBDP_15") (pintype "bidirectional"))
      (node (ref "X1") (pin "3") (pinfunction "3_3") (pintype "passive"))
    )
    (net (code "66") (name "VCC") (class "Default")
      (node (ref "C1") (pin "+") (pinfunction "+_+") (pintype "passive"))
      (node (ref "C14") (pin "1") (pinfunction "1_1") (pintype "passive"))
      (node (ref "C2") (pin "+") (pinfunction "+_+") (pintype "passive"))
      (node (ref "C3") (pin "2") (pinfunction "2_2") (pintype "passive"))
      (node (ref "C4") (pin "2") (pinfunction "2_2") (pintype "passive"))
      (node (ref "C7") (pin "+") (pinfunction "+_+") (pintype "passive"))
      (node (ref "C8") (pin "1") (pinfunction "1_1") (pintype "passive"))
      (node (ref "D1") (pin "C") (pinfunction "C_C") (pintype "passive"))
      (node (ref "IC1") (pin "1") (pinfunction "VI_1") (pintype "input"))
      (node (ref "IC4") (pin "1") (pinfunction "VI_1") (pintype "input"))
    )
    (net (code "67") (name "unconnected-(IC3-ADC6-Pad19)") (class "Default")
      (node (ref "IC3") (pin "19") (pinfunction "ADC6_19") (pintype "bidirectional"))
    )
    (net (code "68") (name "unconnected-(IC3-ADC7-Pad22)") (class "Default")
      (node (ref "IC3") (pin "22") (pinfunction "ADC7_22") (pintype "bidirectional"))
    )
    (net (code "69") (name "unconnected-(IC3-PB0(ICP)-Pad12)") (class "Default")
      (node (ref "IC3") (pin "12") (pinfunction "PB0(ICP)_12") (pintype "bidirectional"))
    )
    (net (code "70") (name "unconnected-(IC3-PC0(ADC0)-Pad23)") (class "Default")
      (node (ref "IC3") (pin "23") (pinfunction "PC0(ADC0)_23") (pintype "bidirectional"))
    )
    (net (code "71") (name "unconnected-(IC3-PC1(ADC1)-Pad24)") (class "Default")
      (node (ref "IC3") (pin "24") (pinfunction "PC1(ADC1)_24") (pintype "bidirectional"))
    )
    (net (code "72") (name "unconnected-(IC3-PC2(ADC2)-Pad25)") (class "Default")
      (node (ref "IC3") (pin "25") (pinfunction "PC2(ADC2)_25") (pintype "bidirectional"))
    )
    (net (code "73") (name "unconnected-(IC3-PC3(ADC3)-Pad26)") (class "Default")
      (node (ref "IC3") (pin "26") (pinfunction "PC3(ADC3)_26") (pintype "bidirectional"))
    )
    (net (code "74") (name "unconnected-(IC3-PD5(T1)-Pad9)") (class "Default")
      (node (ref "IC3") (pin "9") (pinfunction "PD5(T1)_9") (pintype "bidirectional"))
    )
    (net (code "75") (name "unconnected-(IC3-PD7(AIN1)-Pad11)") (class "Default")
      (node (ref "IC3") (pin "11") (pinfunction "PD7(AIN1)_11") (pintype "bidirectional"))
    )
    (net (code "76") (name "unconnected-(IC5-ADC-Pad2)") (class "Default")
      (node (ref "IC5") (pin "2") (pinfunction "ADC_2") (pintype "bidirectional"))
    )
    (net (code "77") (name "unconnected-(IC5-GPIO0-Pad12)") (class "Default")
      (node (ref "IC5") (pin "12") (pinfunction "GPIO0_12") (pintype "bidirectional"))
    )
    (net (code "78") (name "unconnected-(IC5-GPIO4-Pad14)") (class "Default")
      (node (ref "IC5") (pin "14") (pinfunction "GPIO4_14") (pintype "bidirectional"))
    )
    (net (code "79") (name "unconnected-(IC5-GPIO5-Pad13)") (class "Default")
      (node (ref "IC5") (pin "13") (pinfunction "GPIO5_13") (pintype "bidirectional"))
    )
    (net (code "80") (name "unconnected-(IC5-GPIO12-Pad6)") (class "Default")
      (node (ref "IC5") (pin "6") (pinfunction "GPIO12_6") (pintype "bidirectional"))
    )
    (net (code "81") (name "unconnected-(IC5-GPIO13-Pad7)") (class "Default")
      (node (ref "IC5") (pin "7") (pinfunction "GPIO13_7") (pintype "bidirectional"))
    )
    (net (code "82") (name "unconnected-(IC5-GPIO14-Pad5)") (class "Default")
      (node (ref "IC5") (pin "5") (pinfunction "GPIO14_5") (pintype "bidirectional"))
    )
    (net (code "83") (name "unconnected-(IC5-GPIO16-Pad4)") (class "Default")
      (node (ref "IC5") (pin "4") (pinfunction "GPIO16_4") (pintype "bidirectional"))
    )
    (net (code "84") (name "unconnected-(IC6-~{INT}-Pad13)") (class "Default")
      (node (ref "IC6") (pin "13") (pinfunction "~{INT}_13") (pintype "output"))
    )
    (net (code "85") (name "unconnected-(IC7-~{INT}-Pad13)") (class "Default")
      (node (ref "IC7") (pin "13") (pinfunction "~{INT}_13") (pintype "output"))
    )
    (net (code "86") (name "unconnected-(IC8-~{INT}-Pad13)") (class "Default")
      (node (ref "IC8") (pin "13") (pinfunction "~{INT}_13") (pintype "output"))
    )
    (net (code "87") (name "unconnected-(IC10-PadNO)") (class "Default")
      (node (ref "IC10") (pin "NO") (pinfunction "NO_NO") (pintype "bidirectional"))
    )
    (net (code "88") (name "unconnected-(P1-DAT1-Pad8)") (class "Default")
      (node (ref "P1") (pin "8") (pinfunction "DAT1_8") (pintype "bidirectional"))
    )
    (net (code "89") (name "unconnected-(U1-CBUS2-Pad13)") (class "Default")
      (node (ref "U1") (pin "13") (pinfunction "CBUS2_13") (pintype "bidirectional"))
    )
    (net (code "90") (name "unconnected-(U1-CBUS3-Pad14)") (class "Default")
      (node (ref "U1") (pin "14") (pinfunction "CBUS3_14") (pintype "bidirectional"))
    )
    (net (code "91") (name "unconnected-(U1-CBUS4-Pad12)") (class "Default")
      (node (ref "U1") (pin "12") (pinfunction "CBUS4_12") (pintype "bidirectional"))
    )
    (net (code "92") (name "unconnected-(U1-CTS#-Pad11)") (class "Default")
      (node (ref "U1") (pin "11") (pinfunction "CTS#_11") (pintype "input"))
    )
    (net (code "93") (name "unconnected-(U1-DCD#-Pad10)") (class "Default")
      (node (ref "U1") (pin "10") (pinfunction "DCD#_10") (pintype "input"))
    )
    (net (code "94") (name "unconnected-(U1-DSR#-Pad9)") (class "Default")
      (node (ref "U1") (pin "9") (pinfunction "DSR#_9") (pintype "input"))
    )
    (net (code "95") (name "unconnected-(U1-DTR#-Pad2)") (class "Default")
      (node (ref "U1") (pin "2") (pinfunction "DTR#_2") (pintype "output"))
    )
    (net (code "96") (name "unconnected-(U1-OSCI-Pad27)") (class "Default")
      (node (ref "U1") (pin "27") (pinfunction "OSCI_27") (pintype "input"))
    )
    (net (code "97") (name "unconnected-(U1-OSCO-Pad28)") (class "Default")
      (node (ref "U1") (pin "28") (pinfunction "OSCO_28") (pintype "output"))
    )
    (net (code "98") (name "unconnected-(U1-RESET#-Pad19)") (class "Default")
      (node (ref "U1") (pin "19") (pinfunction "RESET#_19") (pintype "input"))
    )
    (net (code "99") (name "unconnected-(U1-RI#-Pad6)") (class "Default")
      (node (ref "U1") (pin "6") (pinfunction "RI#_6") (pintype "input"))
    )
    (net (code "100") (name "unconnected-(U1-RTS#-Pad3)") (class "Default")
      (node (ref "U1") (pin "3") (pinfunction "RTS#_3") (pintype "output"))
    )
    (net (code "101") (name "unconnected-(X1-Pad1)") (class "Default")
      (node (ref "X1") (pin "1") (pinfunction "1_1") (pintype "passive"))
    )
  )
)
